# ProDoc__V4_0_2025-09-29.net
KiCad netlist of a schematic drawn in EasyEDA Pro
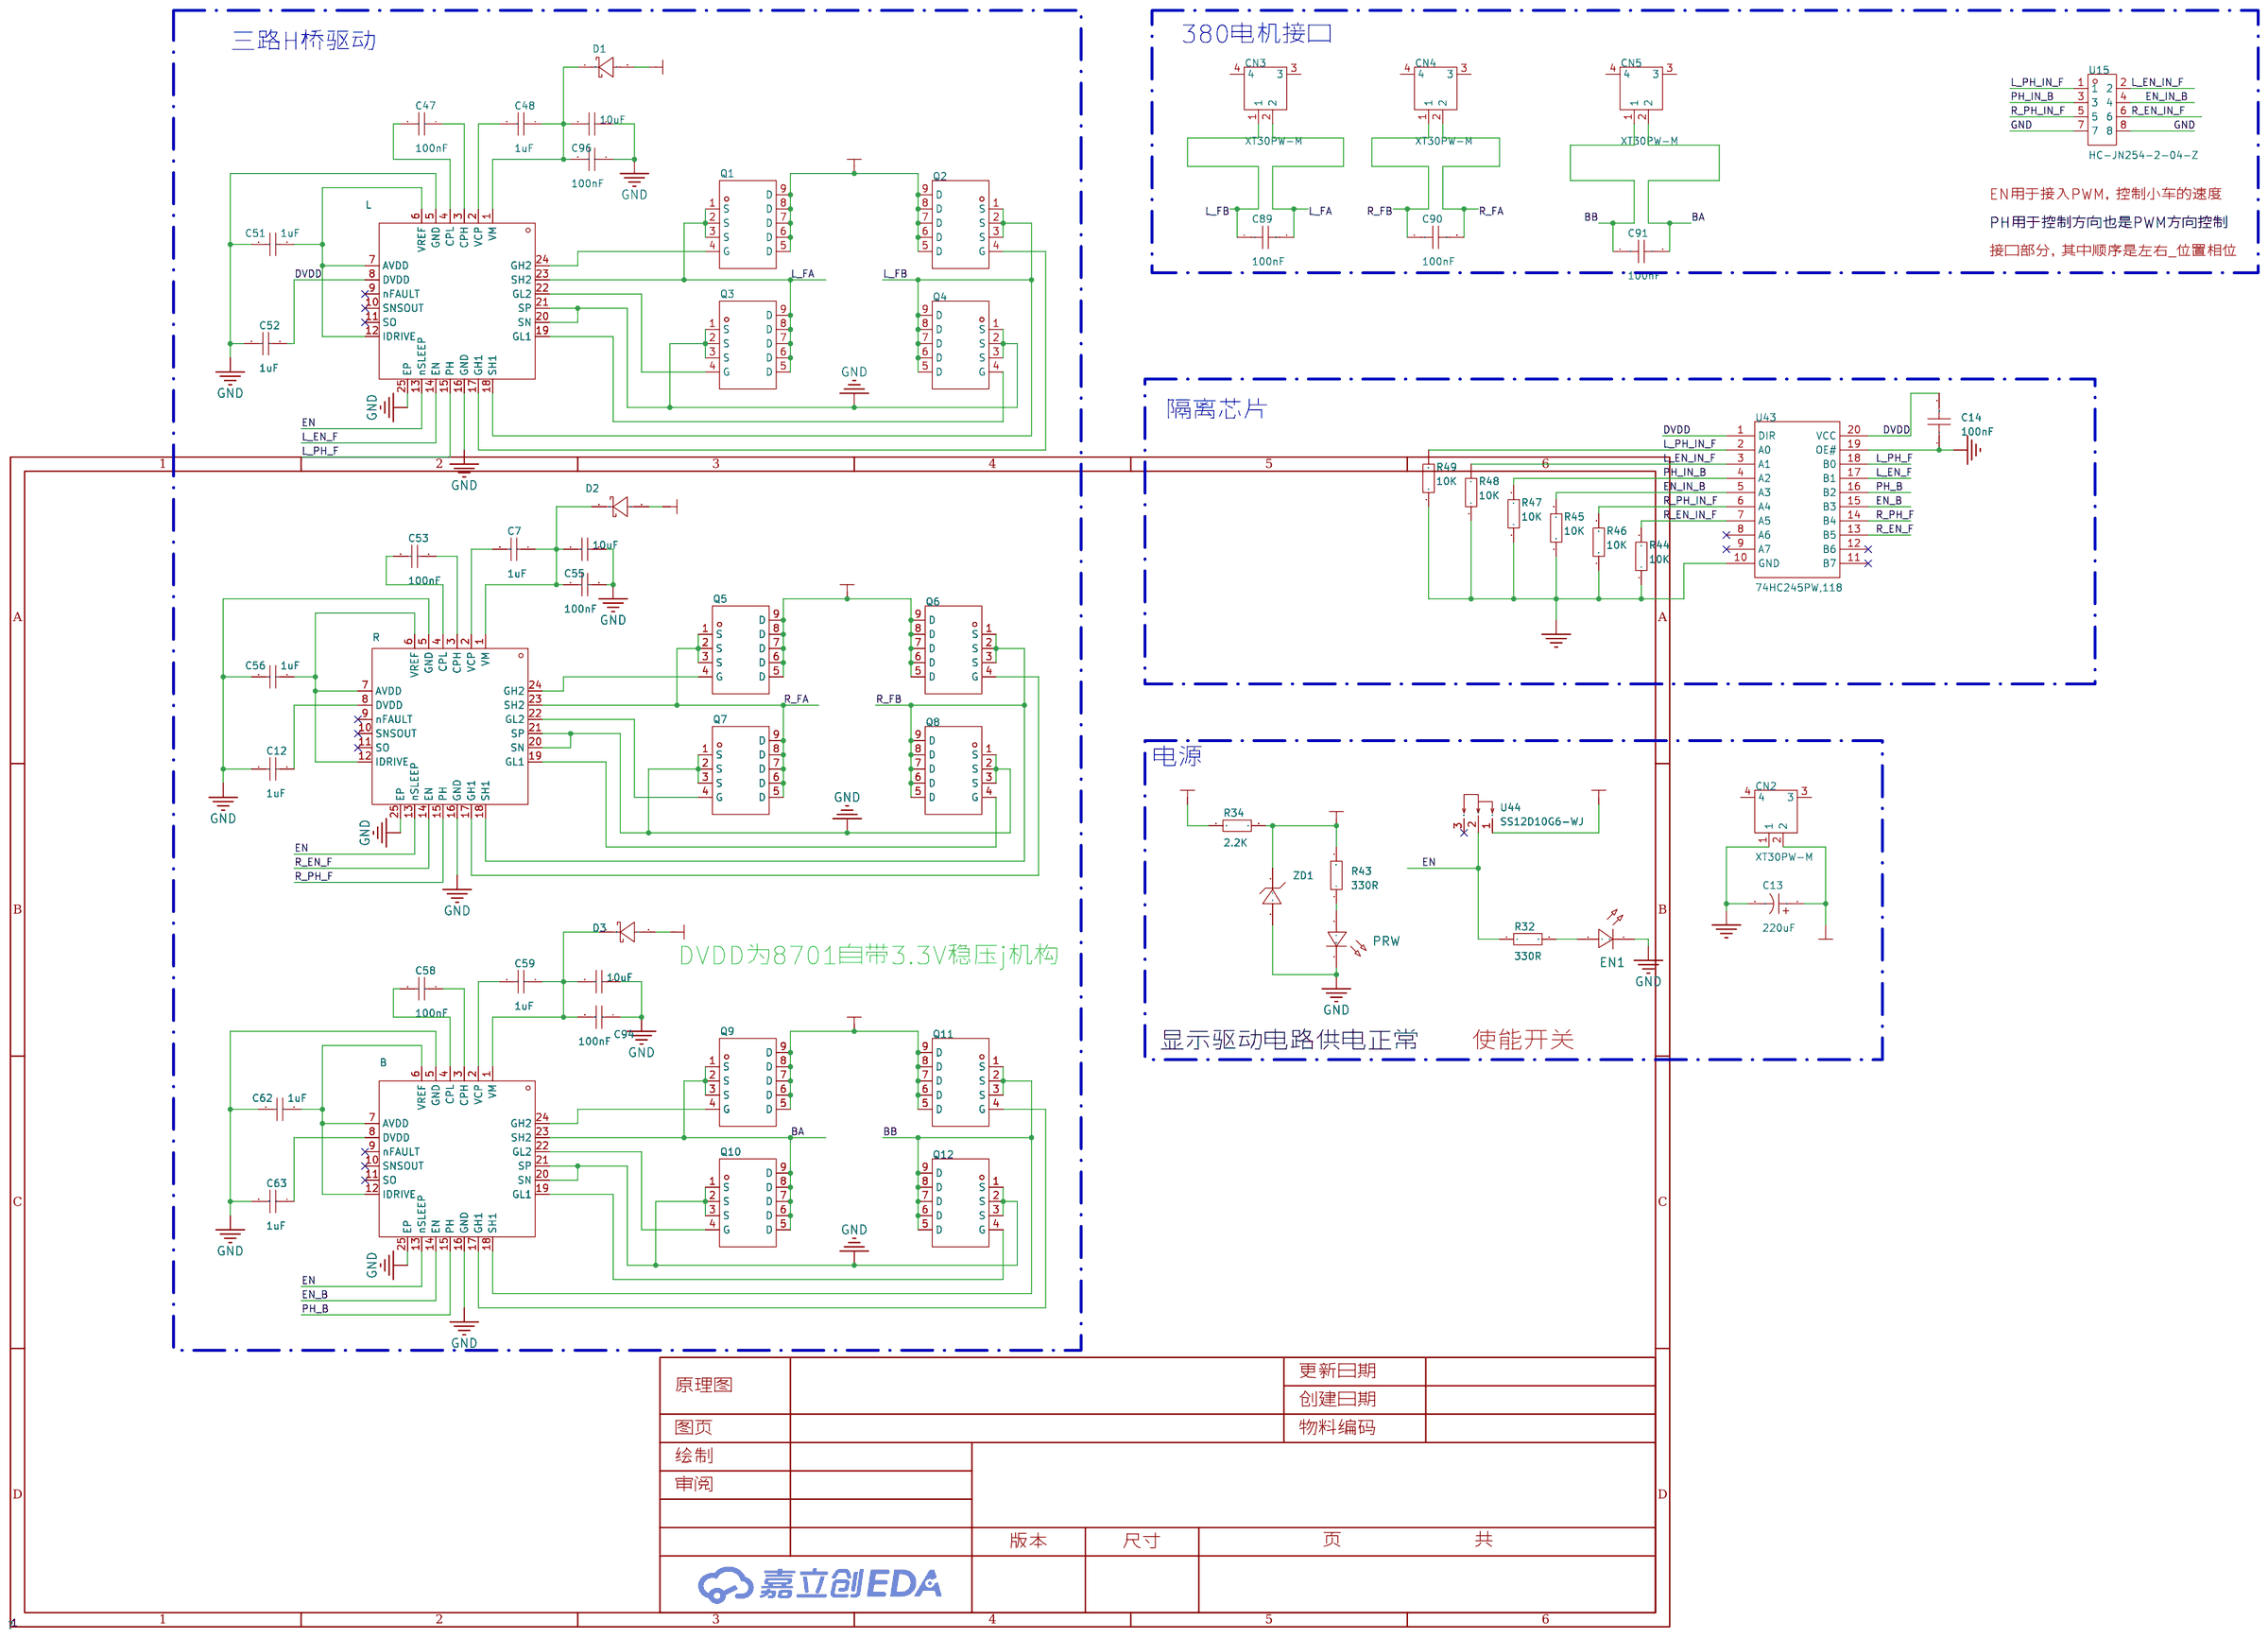
[diagram p0: schematic sheet]

(export (version "E")
  (design (tool "Eeschema 10.0.6"))
  (components
    (comp (ref "B")
      (value "DRV8701ERGET")
      (footprint "easyedapro:VQFN-24_L4.0-W4.0-P0.50-LS4.0-BL-EP")
      (description "DRV8701 DRV8701 H 桥栅极驱动器")
      (fields (field (name "Manufacturer") "TI(德州仪器)"))
      (libsource (lib "easyedapro") (part "DRV8701ERGET"))
    )
    (comp (ref "C7")
      (value "1uF")
      (footprint "easyedapro:C0805")
      (description "容值:100nF;精度:±10%;额定电压:50V;温度系数:X7R;")
      (fields
        (field (name "Manufacturer Part") "CC0805KRX7R9BB104")
        (field (name "Manufacturer") "YAGEO(国巨)")
      )
      (libsource (lib "easyedapro") (part "CC0805KRX7R9BB104"))
    )
    (comp (ref "C12")
      (value "1uF")
      (footprint "easyedapro:C0805")
      (description "容值:100nF;精度:±10%;额定电压:50V;温度系数:X7R;")
      (fields
        (field (name "Manufacturer Part") "CC0805KRX7R9BB104")
        (field (name "Manufacturer") "YAGEO(国巨)")
      )
      (libsource (lib "easyedapro") (part "CC0805KRX7R9BB104"))
    )
    (comp (ref "C13")
      (value "220uF")
      (footprint "easyedapro:CAP-TH_BD8.0-P3.50-D0.5-FD")
      (description "容值:220uF;精度:±20%;额定电压:35V;纹波电流:280mA@120kHz;等效串联电阻:-;")
      (fields (field (name "Manufacturer Part") "01EC1230") (field (name "Manufacturer") "KNSCHA(科尼盛)"))
      (libsource (lib "easyedapro") (part "01EC1230"))
    )
    (comp (ref "C14")
      (value "100nF")
      (footprint "easyedapro:C0805")
      (libsource (lib "easyedapro") (part "CapAcitance"))
    )
    (comp (ref "C47")
      (value "100nF")
      (footprint "easyedapro:C0805")
      (description "容值:100nF;精度:±10%;额定电压:50V;温度系数:X7R;")
      (fields
        (field (name "Manufacturer Part") "CC0805KRX7R9BB104")
        (field (name "Manufacturer") "YAGEO(国巨)")
      )
      (libsource (lib "easyedapro") (part "CC0805KRX7R9BB104"))
    )
    (comp (ref "C48")
      (value "1uF")
      (footprint "easyedapro:C0805")
      (description "容值:100nF;精度:±10%;额定电压:50V;温度系数:X7R;")
      (fields
        (field (name "Manufacturer Part") "CC0805KRX7R9BB104")
        (field (name "Manufacturer") "YAGEO(国巨)")
      )
      (libsource (lib "easyedapro") (part "CC0805KRX7R9BB104"))
    )
    (comp (ref "C51")
      (value "1uF")
      (footprint "easyedapro:C0805")
      (description "容值:100nF;精度:±10%;额定电压:50V;温度系数:X7R;")
      (fields
        (field (name "Manufacturer Part") "CC0805KRX7R9BB104")
        (field (name "Manufacturer") "YAGEO(国巨)")
      )
      (libsource (lib "easyedapro") (part "CC0805KRX7R9BB104"))
    )
    (comp (ref "C52")
      (value "1uF")
      (footprint "easyedapro:C0805")
      (description "容值:100nF;精度:±10%;额定电压:50V;温度系数:X7R;")
      (fields
        (field (name "Manufacturer Part") "CC0805KRX7R9BB104")
        (field (name "Manufacturer") "YAGEO(国巨)")
      )
      (libsource (lib "easyedapro") (part "CC0805KRX7R9BB104"))
    )
    (comp (ref "C53")
      (value "100nF")
      (footprint "easyedapro:C0805")
      (description "容值:100nF;精度:±10%;额定电压:50V;温度系数:X7R;")
      (fields
        (field (name "Manufacturer Part") "CC0805KRX7R9BB104")
        (field (name "Manufacturer") "YAGEO(国巨)")
      )
      (libsource (lib "easyedapro") (part "CC0805KRX7R9BB104"))
    )
    (comp (ref "C54")
      (value "10uF")
      (footprint "easyedapro:C0805")
      (description "容值:100nF;精度:±10%;额定电压:50V;温度系数:X7R;")
      (fields
        (field (name "Manufacturer Part") "CC0805KRX7R9BB104")
        (field (name "Manufacturer") "YAGEO(国巨)")
      )
      (libsource (lib "easyedapro") (part "CC0805KRX7R9BB104"))
    )
    (comp (ref "C55")
      (value "100nF")
      (footprint "easyedapro:C0805")
      (description "容值:100nF;精度:±10%;额定电压:50V;温度系数:X7R;")
      (fields
        (field (name "Manufacturer Part") "CC0805KRX7R9BB104")
        (field (name "Manufacturer") "YAGEO(国巨)")
      )
      (libsource (lib "easyedapro") (part "CC0805KRX7R9BB104"))
    )
    (comp (ref "C56")
      (value "1uF")
      (footprint "easyedapro:C0805")
      (description "容值:100nF;精度:±10%;额定电压:50V;温度系数:X7R;")
      (fields
        (field (name "Manufacturer Part") "CC0805KRX7R9BB104")
        (field (name "Manufacturer") "YAGEO(国巨)")
      )
      (libsource (lib "easyedapro") (part "CC0805KRX7R9BB104"))
    )
    (comp (ref "C58")
      (value "100nF")
      (footprint "easyedapro:C0805")
      (description "容值:100nF;精度:±10%;额定电压:50V;温度系数:X7R;")
      (fields
        (field (name "Manufacturer Part") "CC0805KRX7R9BB104")
        (field (name "Manufacturer") "YAGEO(国巨)")
      )
      (libsource (lib "easyedapro") (part "CC0805KRX7R9BB104"))
    )
    (comp (ref "C59")
      (value "1uF")
      (footprint "easyedapro:C0805")
      (description "容值:100nF;精度:±10%;额定电压:50V;温度系数:X7R;")
      (fields
        (field (name "Manufacturer Part") "CC0805KRX7R9BB104")
        (field (name "Manufacturer") "YAGEO(国巨)")
      )
      (libsource (lib "easyedapro") (part "CC0805KRX7R9BB104"))
    )
    (comp (ref "C62")
      (value "1uF")
      (footprint "easyedapro:C0805")
      (description "容值:100nF;精度:±10%;额定电压:50V;温度系数:X7R;")
      (fields
        (field (name "Manufacturer Part") "CC0805KRX7R9BB104")
        (field (name "Manufacturer") "YAGEO(国巨)")
      )
      (libsource (lib "easyedapro") (part "CC0805KRX7R9BB104"))
    )
    (comp (ref "C63")
      (value "1uF")
      (footprint "easyedapro:C0805")
      (description "容值:100nF;精度:±10%;额定电压:50V;温度系数:X7R;")
      (fields
        (field (name "Manufacturer Part") "CC0805KRX7R9BB104")
        (field (name "Manufacturer") "YAGEO(国巨)")
      )
      (libsource (lib "easyedapro") (part "CC0805KRX7R9BB104"))
    )
    (comp (ref "C89")
      (value "100nF")
      (footprint "easyedapro:C0805")
      (libsource (lib "easyedapro") (part "CapAcitance"))
    )
    (comp (ref "C90")
      (value "100nF")
      (footprint "easyedapro:C0805")
      (libsource (lib "easyedapro") (part "CapAcitance"))
    )
    (comp (ref "C91")
      (value "100nF")
      (footprint "easyedapro:C0805")
      (libsource (lib "easyedapro") (part "CapAcitance"))
    )
    (comp (ref "C93")
      (value "10uF")
      (footprint "easyedapro:C0805")
      (description "容值:100nF;精度:±10%;额定电压:50V;温度系数:X7R;")
      (fields
        (field (name "Manufacturer Part") "CC0805KRX7R9BB104")
        (field (name "Manufacturer") "YAGEO(国巨)")
      )
      (libsource (lib "easyedapro") (part "CC0805KRX7R9BB104"))
    )
    (comp (ref "C94")
      (value "100nF")
      (footprint "easyedapro:C0805")
      (description "容值:100nF;精度:±10%;额定电压:50V;温度系数:X7R;")
      (fields
        (field (name "Manufacturer Part") "CC0805KRX7R9BB104")
        (field (name "Manufacturer") "YAGEO(国巨)")
      )
      (libsource (lib "easyedapro") (part "CC0805KRX7R9BB104"))
    )
    (comp (ref "C95")
      (value "10uF")
      (footprint "easyedapro:C0805")
      (description "容值:100nF;精度:±10%;额定电压:50V;温度系数:X7R;")
      (fields
        (field (name "Manufacturer Part") "CC0805KRX7R9BB104")
        (field (name "Manufacturer") "YAGEO(国巨)")
      )
      (libsource (lib "easyedapro") (part "CC0805KRX7R9BB104"))
    )
    (comp (ref "C96")
      (value "100nF")
      (footprint "easyedapro:C0805")
      (description "容值:100nF;精度:±10%;额定电压:50V;温度系数:X7R;")
      (fields
        (field (name "Manufacturer Part") "CC0805KRX7R9BB104")
        (field (name "Manufacturer") "YAGEO(国巨)")
      )
      (libsource (lib "easyedapro") (part "CC0805KRX7R9BB104"))
    )
    (comp (ref "CN2")
      (value "XT30PW-M")
      (footprint "easyedapro:CONN-TH_XT30PW-M")
      (description "类别:-;类型1:-;")
      (fields (field (name "Manufacturer") "AMASS(艾迈斯)"))
      (libsource (lib "easyedapro") (part "XT30PW-M"))
    )
    (comp (ref "CN3")
      (value "XT30PW-M")
      (footprint "easyedapro:CONN-TH_XT30PW-M")
      (description "类别:-;类型1:-;")
      (fields (field (name "Manufacturer") "AMASS(艾迈斯)"))
      (libsource (lib "easyedapro") (part "XT30PW-M"))
    )
    (comp (ref "CN4")
      (value "XT30PW-M")
      (footprint "easyedapro:CONN-TH_XT30PW-M")
      (description "类别:-;类型1:-;")
      (fields (field (name "Manufacturer") "AMASS(艾迈斯)"))
      (libsource (lib "easyedapro") (part "XT30PW-M"))
    )
    (comp (ref "CN5")
      (value "XT30PW-M")
      (footprint "easyedapro:CONN-TH_XT30PW-M")
      (description "类别:-;类型1:-;")
      (fields (field (name "Manufacturer") "AMASS(艾迈斯)"))
      (libsource (lib "easyedapro") (part "XT30PW-M"))
    )
    (comp (ref "D1")
      (value "1N5819WS")
      (footprint "easyedapro:SOD-323_L1.6-W1.3-LS2.7-RD")
      (description "二极管配置:独立式;直流反向耐压(Vr):40V;平均整流电流(Io):-;正向压降(Vf):600mV@200mA;反向电流(Ir):5A@30V;")
      (fields (field (name "Manufacturer") "YFW佑风微"))
      (libsource (lib "easyedapro") (part "1N5819WS_C1884554"))
    )
    (comp (ref "D2")
      (value "1N5819WS")
      (footprint "easyedapro:SOD-323_L1.6-W1.3-LS2.7-RD")
      (description "二极管配置:独立式;直流反向耐压(Vr):40V;平均整流电流(Io):-;正向压降(Vf):600mV@200mA;反向电流(Ir):5A@30V;")
      (fields (field (name "Manufacturer") "YFW佑风微"))
      (libsource (lib "easyedapro") (part "1N5819WS_C1884554"))
    )
    (comp (ref "D3")
      (value "1N5819WS")
      (footprint "easyedapro:SOD-323_L1.6-W1.3-LS2.7-RD")
      (description "二极管配置:独立式;直流反向耐压(Vr):40V;平均整流电流(Io):-;正向压降(Vf):600mV@200mA;反向电流(Ir):5A@30V;")
      (fields (field (name "Manufacturer") "YFW佑风微"))
      (libsource (lib "easyedapro") (part "1N5819WS_C1884554"))
    )
    (comp (ref "EN1")
      (value "~")
      (footprint "easyedapro:LED0603-RD_BLUE")
      (libsource (lib "easyedapro") (part "LED_R"))
    )
    (comp (ref "L")
      (value "DRV8701ERGET")
      (footprint "easyedapro:VQFN-24_L4.0-W4.0-P0.50-LS4.0-BL-EP")
      (description "DRV8701 DRV8701 H 桥栅极驱动器")
      (fields (field (name "Manufacturer") "TI(德州仪器)"))
      (libsource (lib "easyedapro") (part "DRV8701ERGET"))
    )
    (comp (ref "PRW")
      (value "~")
      (footprint "easyedapro:LED0603-RD_BLUE")
      (libsource (lib "easyedapro") (part "LED_R"))
    )
    (comp (ref "Q1")
      (value "TPH1R403NL")
      (footprint "easyedapro:DSOP-8_L5.0-W5.0-P1.27-LS6.0-BL-EP")
      (fields (field (name "Manufacturer") "TOSHIBA(东芝)"))
      (libsource (lib "easyedapro") (part "TPH1R403NL"))
    )
    (comp (ref "Q2")
      (value "TPH1R403NL")
      (footprint "easyedapro:DSOP-8_L5.0-W5.0-P1.27-LS6.0-BL-EP")
      (fields (field (name "Manufacturer") "TOSHIBA(东芝)"))
      (libsource (lib "easyedapro") (part "TPH1R403NL"))
    )
    (comp (ref "Q3")
      (value "TPH1R403NL")
      (footprint "easyedapro:DSOP-8_L5.0-W5.0-P1.27-LS6.0-BL-EP")
      (fields (field (name "Manufacturer") "TOSHIBA(东芝)"))
      (libsource (lib "easyedapro") (part "TPH1R403NL"))
    )
    (comp (ref "Q4")
      (value "TPH1R403NL")
      (footprint "easyedapro:DSOP-8_L5.0-W5.0-P1.27-LS6.0-BL-EP")
      (fields (field (name "Manufacturer") "TOSHIBA(东芝)"))
      (libsource (lib "easyedapro") (part "TPH1R403NL"))
    )
    (comp (ref "Q5")
      (value "TPH1R403NL")
      (footprint "easyedapro:DSOP-8_L5.0-W5.0-P1.27-LS6.0-BL-EP")
      (fields (field (name "Manufacturer") "TOSHIBA(东芝)"))
      (libsource (lib "easyedapro") (part "TPH1R403NL"))
    )
    (comp (ref "Q6")
      (value "TPH1R403NL")
      (footprint "easyedapro:DSOP-8_L5.0-W5.0-P1.27-LS6.0-BL-EP")
      (fields (field (name "Manufacturer") "TOSHIBA(东芝)"))
      (libsource (lib "easyedapro") (part "TPH1R403NL"))
    )
    (comp (ref "Q7")
      (value "TPH1R403NL")
      (footprint "easyedapro:DSOP-8_L5.0-W5.0-P1.27-LS6.0-BL-EP")
      (fields (field (name "Manufacturer") "TOSHIBA(东芝)"))
      (libsource (lib "easyedapro") (part "TPH1R403NL"))
    )
    (comp (ref "Q8")
      (value "TPH1R403NL")
      (footprint "easyedapro:DSOP-8_L5.0-W5.0-P1.27-LS6.0-BL-EP")
      (fields (field (name "Manufacturer") "TOSHIBA(东芝)"))
      (libsource (lib "easyedapro") (part "TPH1R403NL"))
    )
    (comp (ref "Q9")
      (value "TPH1R403NL")
      (footprint "easyedapro:DSOP-8_L5.0-W5.0-P1.27-LS6.0-BL-EP")
      (fields (field (name "Manufacturer") "TOSHIBA(东芝)"))
      (libsource (lib "easyedapro") (part "TPH1R403NL"))
    )
    (comp (ref "Q10")
      (value "TPH1R403NL")
      (footprint "easyedapro:DSOP-8_L5.0-W5.0-P1.27-LS6.0-BL-EP")
      (fields (field (name "Manufacturer") "TOSHIBA(东芝)"))
      (libsource (lib "easyedapro") (part "TPH1R403NL"))
    )
    (comp (ref "Q11")
      (value "TPH1R403NL")
      (footprint "easyedapro:DSOP-8_L5.0-W5.0-P1.27-LS6.0-BL-EP")
      (fields (field (name "Manufacturer") "TOSHIBA(东芝)"))
      (libsource (lib "easyedapro") (part "TPH1R403NL"))
    )
    (comp (ref "Q12")
      (value "TPH1R403NL")
      (footprint "easyedapro:DSOP-8_L5.0-W5.0-P1.27-LS6.0-BL-EP")
      (fields (field (name "Manufacturer") "TOSHIBA(东芝)"))
      (libsource (lib "easyedapro") (part "TPH1R403NL"))
    )
    (comp (ref "R")
      (value "DRV8701ERGET")
      (footprint "easyedapro:VQFN-24_L4.0-W4.0-P0.50-LS4.0-BL-EP")
      (description "DRV8701 DRV8701 H 桥栅极驱动器")
      (fields (field (name "Manufacturer") "TI(德州仪器)"))
      (libsource (lib "easyedapro") (part "DRV8701ERGET"))
    )
    (comp (ref "R32")
      (value "330R")
      (footprint "easyedapro:R0603")
      (libsource (lib "easyedapro") (part "电阻"))
    )
    (comp (ref "R34")
      (value "2.2K")
      (footprint "easyedapro:R0603")
      (libsource (lib "easyedapro") (part "电阻"))
    )
    (comp (ref "R43")
      (value "330R")
      (footprint "easyedapro:R0603")
      (libsource (lib "easyedapro") (part "电阻"))
    )
    (comp (ref "R44") (value "10K") (footprint "easyedapro:R0603") (libsource (lib "easyedapro") (part "电阻")))
    (comp (ref "R45") (value "10K") (footprint "easyedapro:R0603") (libsource (lib "easyedapro") (part "电阻")))
    (comp (ref "R46") (value "10K") (footprint "easyedapro:R0603") (libsource (lib "easyedapro") (part "电阻")))
    (comp (ref "R47") (value "10K") (footprint "easyedapro:R0603") (libsource (lib "easyedapro") (part "电阻")))
    (comp (ref "R48") (value "10K") (footprint "easyedapro:R0603") (libsource (lib "easyedapro") (part "电阻")))
    (comp (ref "R49") (value "10K") (footprint "easyedapro:R0603") (libsource (lib "easyedapro") (part "电阻")))
    (comp (ref "U15")
      (value "HC-JN254-2-04-Z")
      (footprint "easyedapro:IDC-TH_8P-P2.54-V-R2-C4-S2.54")
      (fields (field (name "Manufacturer") "HCTL(华灿天禄)"))
      (libsource (lib "easyedapro") (part "HC-JN254-2-04-Z"))
    )
    (comp (ref "U43")
      (value "74HC245PW,118")
      (footprint "easyedapro:TSSOP-20_L6.5-W4.4-P0.65-LS6.4-BL")
      (description "输入类型:-;电源电压:2V~6V;元件数:1;每个元件位数:8;灌电流(IOL):7.8mA;拉电流(IOH):7.8mA;")
      (fields (field (name "Manufacturer") "Nexperia(安世)"))
      (libsource (lib "easyedapro") (part "74HC245PW,118"))
    )
    (comp (ref "U44")
      (value "SS12D10G6-WJ")
      (footprint "easyedapro:SW-TH_3P-P4.80_HX-SS12D10G6-WJ")
      (description "电路结构:单刀双掷;安装方式:弯插;开关颜色:黑色;额定电流:2A;额定电压:125V;工作寿命:3千次;")
      (fields (field (name "Manufacturer") "SHOU HAN(首韩)"))
      (libsource (lib "easyedapro") (part "SS12D10G6-WJ"))
    )
    (comp (ref "ZD1")
      (value "BZT52C3V3")
      (footprint "easyedapro:SOD-123_L2.8-W1.8-LS3.7-RD")
      (description "二极管配置:独立式;稳压值(标称值):3.3V;稳压值(范围):3.1V~3.5V;精度:-;功率:350mW;反向电流(Ir):5A@1V;阻抗(Zzt):95Ω;")
      (fields (field (name "Manufacturer") "CJ（江苏长电/长晶）"))
      (libsource (lib "easyedapro") (part "BZT52C3V3_C2112"))
    )
  )
  (nets
    (net (code "1") (name "/BA") (class "Default")
      (node (ref "B") (pin "23") (pinfunction "SH2_23") (pintype "input"))
      (node (ref "C91") (pin "2") (pinfunction "2_2") (pintype "input"))
      (node (ref "CN5") (pin "2") (pinfunction "2_2") (pintype "unspecified"))
      (node (ref "Q10") (pin "5") (pinfunction "D_5") (pintype "input"))
      (node (ref "Q10") (pin "6") (pinfunction "D_6") (pintype "input"))
      (node (ref "Q10") (pin "7") (pinfunction "D_7") (pintype "input"))
      (node (ref "Q10") (pin "8") (pinfunction "D_8") (pintype "input"))
      (node (ref "Q10") (pin "9") (pinfunction "D_9") (pintype "input"))
      (node (ref "Q9") (pin "1") (pinfunction "S_1") (pintype "input"))
      (node (ref "Q9") (pin "2") (pinfunction "S_2") (pintype "input"))
      (node (ref "Q9") (pin "3") (pinfunction "S_3") (pintype "input"))
    )
    (net (code "2") (name "/BB") (class "Default")
      (node (ref "B") (pin "18") (pinfunction "SH1_18") (pintype "input"))
      (node (ref "C91") (pin "1") (pinfunction "1_1") (pintype "input"))
      (node (ref "CN5") (pin "1") (pinfunction "1_1") (pintype "unspecified"))
      (node (ref "Q11") (pin "1") (pinfunction "S_1") (pintype "input"))
      (node (ref "Q11") (pin "2") (pinfunction "S_2") (pintype "input"))
      (node (ref "Q11") (pin "3") (pinfunction "S_3") (pintype "input"))
      (node (ref "Q12") (pin "5") (pinfunction "D_5") (pintype "input"))
      (node (ref "Q12") (pin "6") (pinfunction "D_6") (pintype "input"))
      (node (ref "Q12") (pin "7") (pinfunction "D_7") (pintype "input"))
      (node (ref "Q12") (pin "8") (pinfunction "D_8") (pintype "input"))
      (node (ref "Q12") (pin "9") (pinfunction "D_9") (pintype "input"))
    )
    (net (code "3") (name "/DVDD") (class "Default")
      (node (ref "C14") (pin "2") (pinfunction "2_2") (pintype "input"))
      (node (ref "C52") (pin "1") (pinfunction "1_1") (pintype "input"))
      (node (ref "L") (pin "8") (pinfunction "DVDD_8") (pintype "input"))
      (node (ref "U43") (pin "1") (pinfunction "DIR_1") (pintype "unspecified"))
      (node (ref "U43") (pin "20") (pinfunction "VCC_20") (pintype "unspecified"))
    )
    (net (code "4") (name "/EN") (class "Default")
      (node (ref "B") (pin "13") (pinfunction "nSLEEP_13") (pintype "input"))
      (node (ref "L") (pin "13") (pinfunction "nSLEEP_13") (pintype "input"))
      (node (ref "R") (pin "13") (pinfunction "nSLEEP_13") (pintype "input"))
      (node (ref "R32") (pin "1") (pinfunction "1_1") (pintype "input"))
      (node (ref "U44") (pin "2") (pinfunction "2_2") (pintype "unspecified"))
    )
    (net (code "5") (name "/EN_B") (class "Default")
      (node (ref "B") (pin "14") (pinfunction "EN_14") (pintype "input"))
      (node (ref "U43") (pin "15") (pinfunction "B3_15") (pintype "unspecified"))
    )
    (net (code "6") (name "/EN_IN_B") (class "Default")
      (node (ref "R45") (pin "2") (pinfunction "2_2") (pintype "input"))
      (node (ref "U15") (pin "4") (pinfunction "4_4") (pintype "unspecified"))
      (node (ref "U43") (pin "5") (pinfunction "A3_5") (pintype "unspecified"))
    )
    (net (code "7") (name "/L_EN_F") (class "Default")
      (node (ref "L") (pin "14") (pinfunction "EN_14") (pintype "input"))
      (node (ref "U43") (pin "17") (pinfunction "B1_17") (pintype "unspecified"))
    )
    (net (code "8") (name "/L_EN_IN_F") (class "Default")
      (node (ref "R48") (pin "2") (pinfunction "2_2") (pintype "input"))
      (node (ref "U15") (pin "2") (pinfunction "2_2") (pintype "unspecified"))
      (node (ref "U43") (pin "3") (pinfunction "A1_3") (pintype "unspecified"))
    )
    (net (code "9") (name "/L_FA") (class "Default")
      (node (ref "C89") (pin "2") (pinfunction "2_2") (pintype "input"))
      (node (ref "CN3") (pin "2") (pinfunction "2_2") (pintype "unspecified"))
      (node (ref "L") (pin "23") (pinfunction "SH2_23") (pintype "input"))
      (node (ref "Q1") (pin "1") (pinfunction "S_1") (pintype "input"))
      (node (ref "Q1") (pin "2") (pinfunction "S_2") (pintype "input"))
      (node (ref "Q1") (pin "3") (pinfunction "S_3") (pintype "input"))
      (node (ref "Q3") (pin "5") (pinfunction "D_5") (pintype "input"))
      (node (ref "Q3") (pin "6") (pinfunction "D_6") (pintype "input"))
      (node (ref "Q3") (pin "7") (pinfunction "D_7") (pintype "input"))
      (node (ref "Q3") (pin "8") (pinfunction "D_8") (pintype "input"))
      (node (ref "Q3") (pin "9") (pinfunction "D_9") (pintype "input"))
    )
    (net (code "10") (name "/L_FB") (class "Default")
      (node (ref "C89") (pin "1") (pinfunction "1_1") (pintype "input"))
      (node (ref "CN3") (pin "1") (pinfunction "1_1") (pintype "unspecified"))
      (node (ref "L") (pin "18") (pinfunction "SH1_18") (pintype "input"))
      (node (ref "Q2") (pin "1") (pinfunction "S_1") (pintype "input"))
      (node (ref "Q2") (pin "2") (pinfunction "S_2") (pintype "input"))
      (node (ref "Q2") (pin "3") (pinfunction "S_3") (pintype "input"))
      (node (ref "Q4") (pin "5") (pinfunction "D_5") (pintype "input"))
      (node (ref "Q4") (pin "6") (pinfunction "D_6") (pintype "input"))
      (node (ref "Q4") (pin "7") (pinfunction "D_7") (pintype "input"))
      (node (ref "Q4") (pin "8") (pinfunction "D_8") (pintype "input"))
      (node (ref "Q4") (pin "9") (pinfunction "D_9") (pintype "input"))
    )
    (net (code "11") (name "/L_PH_F") (class "Default")
      (node (ref "L") (pin "15") (pinfunction "PH_15") (pintype "input"))
      (node (ref "U43") (pin "18") (pinfunction "B0_18") (pintype "unspecified"))
    )
    (net (code "12") (name "/L_PH_IN_F") (class "Default")
      (node (ref "R49") (pin "2") (pinfunction "2_2") (pintype "input"))
      (node (ref "U15") (pin "1") (pinfunction "1_1") (pintype "unspecified"))
      (node (ref "U43") (pin "2") (pinfunction "A0_2") (pintype "unspecified"))
    )
    (net (code "13") (name "/PH_B") (class "Default")
      (node (ref "B") (pin "15") (pinfunction "PH_15") (pintype "input"))
      (node (ref "U43") (pin "16") (pinfunction "B2_16") (pintype "unspecified"))
    )
    (net (code "14") (name "/PH_IN_B") (class "Default")
      (node (ref "R47") (pin "2") (pinfunction "2_2") (pintype "input"))
      (node (ref "U15") (pin "3") (pinfunction "3_3") (pintype "unspecified"))
      (node (ref "U43") (pin "4") (pinfunction "A2_4") (pintype "unspecified"))
    )
    (net (code "15") (name "/R_EN_F") (class "Default")
      (node (ref "R") (pin "14") (pinfunction "EN_14") (pintype "input"))
      (node (ref "U43") (pin "13") (pinfunction "B5_13") (pintype "unspecified"))
    )
    (net (code "16") (name "/R_EN_IN_F") (class "Default")
      (node (ref "R44") (pin "2") (pinfunction "2_2") (pintype "input"))
      (node (ref "U15") (pin "6") (pinfunction "6_6") (pintype "unspecified"))
      (node (ref "U43") (pin "7") (pinfunction "A5_7") (pintype "unspecified"))
    )
    (net (code "17") (name "/R_FA") (class "Default")
      (node (ref "C90") (pin "2") (pinfunction "2_2") (pintype "input"))
      (node (ref "CN4") (pin "2") (pinfunction "2_2") (pintype "unspecified"))
      (node (ref "Q5") (pin "1") (pinfunction "S_1") (pintype "input"))
      (node (ref "Q5") (pin "2") (pinfunction "S_2") (pintype "input"))
      (node (ref "Q5") (pin "3") (pinfunction "S_3") (pintype "input"))
      (node (ref "Q7") (pin "5") (pinfunction "D_5") (pintype "input"))
      (node (ref "Q7") (pin "6") (pinfunction "D_6") (pintype "input"))
      (node (ref "Q7") (pin "7") (pinfunction "D_7") (pintype "input"))
      (node (ref "Q7") (pin "8") (pinfunction "D_8") (pintype "input"))
      (node (ref "Q7") (pin "9") (pinfunction "D_9") (pintype "input"))
      (node (ref "R") (pin "23") (pinfunction "SH2_23") (pintype "input"))
    )
    (net (code "18") (name "/R_FB") (class "Default")
      (node (ref "C90") (pin "1") (pinfunction "1_1") (pintype "input"))
      (node (ref "CN4") (pin "1") (pinfunction "1_1") (pintype "unspecified"))
      (node (ref "Q6") (pin "1") (pinfunction "S_1") (pintype "input"))
      (node (ref "Q6") (pin "2") (pinfunction "S_2") (pintype "input"))
      (node (ref "Q6") (pin "3") (pinfunction "S_3") (pintype "input"))
      (node (ref "Q8") (pin "5") (pinfunction "D_5") (pintype "input"))
      (node (ref "Q8") (pin "6") (pinfunction "D_6") (pintype "input"))
      (node (ref "Q8") (pin "7") (pinfunction "D_7") (pintype "input"))
      (node (ref "Q8") (pin "8") (pinfunction "D_8") (pintype "input"))
      (node (ref "Q8") (pin "9") (pinfunction "D_9") (pintype "input"))
      (node (ref "R") (pin "18") (pinfunction "SH1_18") (pintype "input"))
    )
    (net (code "19") (name "/R_PH_F") (class "Default")
      (node (ref "R") (pin "15") (pinfunction "PH_15") (pintype "input"))
      (node (ref "U43") (pin "14") (pinfunction "B4_14") (pintype "unspecified"))
    )
    (net (code "20") (name "/R_PH_IN_F") (class "Default")
      (node (ref "R46") (pin "2") (pinfunction "2_2") (pintype "input"))
      (node (ref "U15") (pin "5") (pinfunction "5_5") (pintype "unspecified"))
      (node (ref "U43") (pin "6") (pinfunction "A4_6") (pintype "unspecified"))
    )
    (net (code "21") (name "3.3V") (class "Default")
      (node (ref "R34") (pin "2") (pinfunction "2_2") (pintype "input"))
      (node (ref "R43") (pin "2") (pinfunction "2_2") (pintype "input"))
      (node (ref "U44") (pin "1") (pinfunction "1_1") (pintype "unspecified"))
      (node (ref "ZD1") (pin "1") (pinfunction "K_1") (pintype "input"))
    )
    (net (code "22") (name "GND") (class "Default")
      (node (ref "B") (pin "16") (pinfunction "GND_16") (pintype "input"))
      (node (ref "B") (pin "20") (pinfunction "SN_20") (pintype "input"))
      (node (ref "B") (pin "21") (pinfunction "SP_21") (pintype "input"))
      (node (ref "B") (pin "25") (pinfunction "EP_25") (pintype "input"))
      (node (ref "B") (pin "5") (pinfunction "GND_5") (pintype "input"))
      (node (ref "C12") (pin "2") (pinfunction "2_2") (pintype "input"))
      (node (ref "C13") (pin "2") (pinfunction "2_2") (pintype "input"))
      (node (ref "C14") (pin "1") (pinfunction "1_1") (pintype "input"))
      (node (ref "C51") (pin "2") (pinfunction "2_2") (pintype "input"))
      (node (ref "C52") (pin "2") (pinfunction "2_2") (pintype "input"))
      (node (ref "C54") (pin "1") (pinfunction "1_1") (pintype "input"))
      (node (ref "C55") (pin "1") (pinfunction "1_1") (pintype "input"))
      (node (ref "C56") (pin "2") (pinfunction "2_2") (pintype "input"))
      (node (ref "C62") (pin "2") (pinfunction "2_2") (pintype "input"))
      (node (ref "C63") (pin "2") (pinfunction "2_2") (pintype "input"))
      (node (ref "C93") (pin "1") (pinfunction "1_1") (pintype "input"))
      (node (ref "C94") (pin "1") (pinfunction "1_1") (pintype "input"))
      (node (ref "C95") (pin "1") (pinfunction "1_1") (pintype "input"))
      (node (ref "C96") (pin "1") (pinfunction "1_1") (pintype "input"))
      (node (ref "CN2") (pin "1") (pinfunction "1_1") (pintype "unspecified"))
      (node (ref "EN1") (pin "1") (pinfunction "C_1") (pintype "input"))
      (node (ref "L") (pin "16") (pinfunction "GND_16") (pintype "input"))
      (node (ref "L") (pin "20") (pinfunction "SN_20") (pintype "input"))
      (node (ref "L") (pin "21") (pinfunction "SP_21") (pintype "input"))
      (node (ref "L") (pin "25") (pinfunction "EP_25") (pintype "input"))
      (node (ref "L") (pin "5") (pinfunction "GND_5") (pintype "input"))
      (node (ref "PRW") (pin "1") (pinfunction "C_1") (pintype "input"))
      (node (ref "Q10") (pin "1") (pinfunction "S_1") (pintype "input"))
      (node (ref "Q10") (pin "2") (pinfunction "S_2") (pintype "input"))
      (node (ref "Q10") (pin "3") (pinfunction "S_3") (pintype "input"))
      (node (ref "Q12") (pin "1") (pinfunction "S_1") (pintype "input"))
      (node (ref "Q12") (pin "2") (pinfunction "S_2") (pintype "input"))
      (node (ref "Q12") (pin "3") (pinfunction "S_3") (pintype "input"))
      (node (ref "Q3") (pin "1") (pinfunction "S_1") (pintype "input"))
      (node (ref "Q3") (pin "2") (pinfunction "S_2") (pintype "input"))
      (node (ref "Q3") (pin "3") (pinfunction "S_3") (pintype "input"))
      (node (ref "Q4") (pin "1") (pinfunction "S_1") (pintype "input"))
      (node (ref "Q4") (pin "2") (pinfunction "S_2") (pintype "input"))
      (node (ref "Q4") (pin "3") (pinfunction "S_3") (pintype "input"))
      (node (ref "Q7") (pin "1") (pinfunction "S_1") (pintype "input"))
      (node (ref "Q7") (pin "2") (pinfunction "S_2") (pintype "input"))
      (node (ref "Q7") (pin "3") (pinfunction "S_3") (pintype "input"))
      (node (ref "Q8") (pin "1") (pinfunction "S_1") (pintype "input"))
      (node (ref "Q8") (pin "2") (pinfunction "S_2") (pintype "input"))
      (node (ref "Q8") (pin "3") (pinfunction "S_3") (pintype "input"))
      (node (ref "R") (pin "16") (pinfunction "GND_16") (pintype "input"))
      (node (ref "R") (pin "20") (pinfunction "SN_20") (pintype "input"))
      (node (ref "R") (pin "21") (pinfunction "SP_21") (pintype "input"))
      (node (ref "R") (pin "25") (pinfunction "EP_25") (pintype "input"))
      (node (ref "R") (pin "5") (pinfunction "GND_5") (pintype "input"))
      (node (ref "R44") (pin "1") (pinfunction "1_1") (pintype "input"))
      (node (ref "R45") (pin "1") (pinfunction "1_1") (pintype "input"))
      (node (ref "R46") (pin "1") (pinfunction "1_1") (pintype "input"))
      (node (ref "R47") (pin "1") (pinfunction "1_1") (pintype "input"))
      (node (ref "R48") (pin "1") (pinfunction "1_1") (pintype "input"))
      (node (ref "R49") (pin "1") (pinfunction "1_1") (pintype "input"))
      (node (ref "U15") (pin "7") (pinfunction "7_7") (pintype "unspecified"))
      (node (ref "U15") (pin "8") (pinfunction "8_8") (pintype "unspecified"))
      (node (ref "U43") (pin "10") (pinfunction "GND_10") (pintype "unspecified"))
      (node (ref "U43") (pin "19") (pinfunction "OE#_19") (pintype "unspecified"))
      (node (ref "ZD1") (pin "2") (pinfunction "A_2") (pintype "input"))
    )
    (net (code "23") (name "Net-(B-AVDD)") (class "Default")
      (node (ref "B") (pin "12") (pinfunction "IDRIVE_12") (pintype "input"))
      (node (ref "B") (pin "6") (pinfunction "VREF_6") (pintype "input"))
      (node (ref "B") (pin "7") (pinfunction "AVDD_7") (pintype "input"))
      (node (ref "C62") (pin "1") (pinfunction "1_1") (pintype "input"))
    )
    (net (code "24") (name "Net-(B-CPH)") (class "Default")
      (node (ref "B") (pin "3") (pinfunction "CPH_3") (pintype "input"))
      (node (ref "C58") (pin "1") (pinfunction "1_1") (pintype "input"))
    )
    (net (code "25") (name "Net-(B-CPL)") (class "Default")
      (node (ref "B") (pin "4") (pinfunction "CPL_4") (pintype "input"))
      (node (ref "C58") (pin "2") (pinfunction "2_2") (pintype "input"))
    )
    (net (code "26") (name "Net-(B-DVDD)") (class "Default")
      (node (ref "B") (pin "8") (pinfunction "DVDD_8") (pintype "input"))
      (node (ref "C63") (pin "1") (pinfunction "1_1") (pintype "input"))
    )
    (net (code "27") (name "Net-(B-GH1)") (class "Default")
      (node (ref "B") (pin "17") (pinfunction "GH1_17") (pintype "input"))
      (node (ref "Q11") (pin "4") (pinfunction "G_4") (pintype "input"))
    )
    (net (code "28") (name "Net-(B-GH2)") (class "Default")
      (node (ref "B") (pin "24") (pinfunction "GH2_24") (pintype "input"))
      (node (ref "Q9") (pin "4") (pinfunction "G_4") (pintype "input"))
    )
    (net (code "29") (name "Net-(B-GL1)") (class "Default")
      (node (ref "B") (pin "19") (pinfunction "GL1_19") (pintype "input"))
      (node (ref "Q12") (pin "4") (pinfunction "G_4") (pintype "input"))
    )
    (net (code "30") (name "Net-(B-GL2)") (class "Default")
      (node (ref "B") (pin "22") (pinfunction "GL2_22") (pintype "input"))
      (node (ref "Q10") (pin "4") (pinfunction "G_4") (pintype "input"))
    )
    (net (code "31") (name "Net-(B-VCP)") (class "Default")
      (node (ref "B") (pin "2") (pinfunction "VCP_2") (pintype "input"))
      (node (ref "C59") (pin "2") (pinfunction "2_2") (pintype "input"))
    )
    (net (code "32") (name "Net-(B-VM)") (class "Default")
      (node (ref "B") (pin "1") (pinfunction "VM_1") (pintype "input"))
      (node (ref "C59") (pin "1") (pinfunction "1_1") (pintype "input"))
      (node (ref "C93") (pin "2") (pinfunction "2_2") (pintype "input"))
      (node (ref "C94") (pin "2") (pinfunction "2_2") (pintype "input"))
      (node (ref "D3") (pin "1") (pinfunction "C_1") (pintype "input"))
    )
    (net (code "33") (name "Net-(D1-C)") (class "Default")
      (node (ref "C48") (pin "1") (pinfunction "1_1") (pintype "input"))
      (node (ref "C95") (pin "2") (pinfunction "2_2") (pintype "input"))
      (node (ref "C96") (pin "2") (pinfunction "2_2") (pintype "input"))
      (node (ref "D1") (pin "1") (pinfunction "C_1") (pintype "input"))
      (node (ref "L") (pin "1") (pinfunction "VM_1") (pintype "input"))
    )
    (net (code "34") (name "Net-(D2-C)") (class "Default")
      (node (ref "C54") (pin "2") (pinfunction "2_2") (pintype "input"))
      (node (ref "C55") (pin "2") (pinfunction "2_2") (pintype "input"))
      (node (ref "C7") (pin "1") (pinfunction "1_1") (pintype "input"))
      (node (ref "D2") (pin "1") (pinfunction "C_1") (pintype "input"))
      (node (ref "R") (pin "1") (pinfunction "VM_1") (pintype "input"))
    )
    (net (code "35") (name "Net-(EN1-A)") (class "Default")
      (node (ref "EN1") (pin "2") (pinfunction "A_2") (pintype "input"))
      (node (ref "R32") (pin "2") (pinfunction "2_2") (pintype "input"))
    )
    (net (code "36") (name "Net-(L-AVDD)") (class "Default")
      (node (ref "C51") (pin "1") (pinfunction "1_1") (pintype "input"))
      (node (ref "L") (pin "12") (pinfunction "IDRIVE_12") (pintype "input"))
      (node (ref "L") (pin "6") (pinfunction "VREF_6") (pintype "input"))
      (node (ref "L") (pin "7") (pinfunction "AVDD_7") (pintype "input"))
    )
    (net (code "37") (name "Net-(L-CPH)") (class "Default")
      (node (ref "C47") (pin "1") (pinfunction "1_1") (pintype "input"))
      (node (ref "L") (pin "3") (pinfunction "CPH_3") (pintype "input"))
    )
    (net (code "38") (name "Net-(L-CPL)") (class "Default")
      (node (ref "C47") (pin "2") (pinfunction "2_2") (pintype "input"))
      (node (ref "L") (pin "4") (pinfunction "CPL_4") (pintype "input"))
    )
    (net (code "39") (name "Net-(L-GH1)") (class "Default")
      (node (ref "L") (pin "17") (pinfunction "GH1_17") (pintype "input"))
      (node (ref "Q2") (pin "4") (pinfunction "G_4") (pintype "input"))
    )
    (net (code "40") (name "Net-(L-GH2)") (class "Default")
      (node (ref "L") (pin "24") (pinfunction "GH2_24") (pintype "input"))
      (node (ref "Q1") (pin "4") (pinfunction "G_4") (pintype "input"))
    )
    (net (code "41") (name "Net-(L-GL1)") (class "Default")
      (node (ref "L") (pin "19") (pinfunction "GL1_19") (pintype "input"))
      (node (ref "Q4") (pin "4") (pinfunction "G_4") (pintype "input"))
    )
    (net (code "42") (name "Net-(L-GL2)") (class "Default")
      (node (ref "L") (pin "22") (pinfunction "GL2_22") (pintype "input"))
      (node (ref "Q3") (pin "4") (pinfunction "G_4") (pintype "input"))
    )
    (net (code "43") (name "Net-(L-VCP)") (class "Default")
      (node (ref "C48") (pin "2") (pinfunction "2_2") (pintype "input"))
      (node (ref "L") (pin "2") (pinfunction "VCP_2") (pintype "input"))
    )
    (net (code "44") (name "Net-(PRW-A)") (class "Default")
      (node (ref "PRW") (pin "2") (pinfunction "A_2") (pintype "input"))
      (node (ref "R43") (pin "1") (pinfunction "1_1") (pintype "input"))
    )
    (net (code "45") (name "Net-(Q5-G)") (class "Default")
      (node (ref "Q5") (pin "4") (pinfunction "G_4") (pintype "input"))
      (node (ref "R") (pin "24") (pinfunction "GH2_24") (pintype "input"))
    )
    (net (code "46") (name "Net-(Q6-G)") (class "Default")
      (node (ref "Q6") (pin "4") (pinfunction "G_4") (pintype "input"))
      (node (ref "R") (pin "17") (pinfunction "GH1_17") (pintype "input"))
    )
    (net (code "47") (name "Net-(Q7-G)") (class "Default")
      (node (ref "Q7") (pin "4") (pinfunction "G_4") (pintype "input"))
      (node (ref "R") (pin "22") (pinfunction "GL2_22") (pintype "input"))
    )
    (net (code "48") (name "Net-(Q8-G)") (class "Default")
      (node (ref "Q8") (pin "4") (pinfunction "G_4") (pintype "input"))
      (node (ref "R") (pin "19") (pinfunction "GL1_19") (pintype "input"))
    )
    (net (code "49") (name "Net-(R-AVDD)") (class "Default")
      (node (ref "C56") (pin "1") (pinfunction "1_1") (pintype "input"))
      (node (ref "R") (pin "12") (pinfunction "IDRIVE_12") (pintype "input"))
      (node (ref "R") (pin "6") (pinfunction "VREF_6") (pintype "input"))
      (node (ref "R") (pin "7") (pinfunction "AVDD_7") (pintype "input"))
    )
    (net (code "50") (name "Net-(R-CPH)") (class "Default")
      (node (ref "C53") (pin "1") (pinfunction "1_1") (pintype "input"))
      (node (ref "R") (pin "3") (pinfunction "CPH_3") (pintype "input"))
    )
    (net (code "51") (name "Net-(R-CPL)") (class "Default")
      (node (ref "C53") (pin "2") (pinfunction "2_2") (pintype "input"))
      (node (ref "R") (pin "4") (pinfunction "CPL_4") (pintype "input"))
    )
    (net (code "52") (name "Net-(R-DVDD)") (class "Default")
      (node (ref "C12") (pin "1") (pinfunction "1_1") (pintype "input"))
      (node (ref "R") (pin "8") (pinfunction "DVDD_8") (pintype "input"))
    )
    (net (code "53") (name "Net-(R-VCP)") (class "Default")
      (node (ref "C7") (pin "2") (pinfunction "2_2") (pintype "input"))
      (node (ref "R") (pin "2") (pinfunction "VCP_2") (pintype "input"))
    )
    (net (code "54") (name "VIN") (class "Default")
      (node (ref "C13") (pin "1") (pinfunction "1_1") (pintype "input"))
      (node (ref "CN2") (pin "2") (pinfunction "2_2") (pintype "unspecified"))
      (node (ref "D1") (pin "2") (pinfunction "A_2") (pintype "input"))
      (node (ref "D2") (pin "2") (pinfunction "A_2") (pintype "input"))
      (node (ref "D3") (pin "2") (pinfunction "A_2") (pintype "input"))
      (node (ref "Q1") (pin "5") (pinfunction "D_5") (pintype "input"))
      (node (ref "Q1") (pin "6") (pinfunction "D_6") (pintype "input"))
      (node (ref "Q1") (pin "7") (pinfunction "D_7") (pintype "input"))
      (node (ref "Q1") (pin "8") (pinfunction "D_8") (pintype "input"))
      (node (ref "Q1") (pin "9") (pinfunction "D_9") (pintype "input"))
      (node (ref "Q11") (pin "5") (pinfunction "D_5") (pintype "input"))
      (node (ref "Q11") (pin "6") (pinfunction "D_6") (pintype "input"))
      (node (ref "Q11") (pin "7") (pinfunction "D_7") (pintype "input"))
      (node (ref "Q11") (pin "8") (pinfunction "D_8") (pintype "input"))
      (node (ref "Q11") (pin "9") (pinfunction "D_9") (pintype "input"))
      (node (ref "Q2") (pin "5") (pinfunction "D_5") (pintype "input"))
      (node (ref "Q2") (pin "6") (pinfunction "D_6") (pintype "input"))
      (node (ref "Q2") (pin "7") (pinfunction "D_7") (pintype "input"))
      (node (ref "Q2") (pin "8") (pinfunction "D_8") (pintype "input"))
      (node (ref "Q2") (pin "9") (pinfunction "D_9") (pintype "input"))
      (node (ref "Q5") (pin "5") (pinfunction "D_5") (pintype "input"))
      (node (ref "Q5") (pin "6") (pinfunction "D_6") (pintype "input"))
      (node (ref "Q5") (pin "7") (pinfunction "D_7") (pintype "input"))
      (node (ref "Q5") (pin "8") (pinfunction "D_8") (pintype "input"))
      (node (ref "Q5") (pin "9") (pinfunction "D_9") (pintype "input"))
      (node (ref "Q6") (pin "5") (pinfunction "D_5") (pintype "input"))
      (node (ref "Q6") (pin "6") (pinfunction "D_6") (pintype "input"))
      (node (ref "Q6") (pin "7") (pinfunction "D_7") (pintype "input"))
      (node (ref "Q6") (pin "8") (pinfunction "D_8") (pintype "input"))
      (node (ref "Q6") (pin "9") (pinfunction "D_9") (pintype "input"))
      (node (ref "Q9") (pin "5") (pinfunction "D_5") (pintype "input"))
      (node (ref "Q9") (pin "6") (pinfunction "D_6") (pintype "input"))
      (node (ref "Q9") (pin "7") (pinfunction "D_7") (pintype "input"))
      (node (ref "Q9") (pin "8") (pinfunction "D_8") (pintype "input"))
      (node (ref "Q9") (pin "9") (pinfunction "D_9") (pintype "input"))
      (node (ref "R34") (pin "1") (pinfunction "1_1") (pintype "input"))
    )
    (net (code "55") (name "unconnected-(B-SNSOUT-Pad10)") (class "Default")
      (node (ref "B") (pin "10") (pinfunction "SNSOUT_10") (pintype "input+no_connect"))
    )
    (net (code "56") (name "unconnected-(B-SO-Pad11)") (class "Default")
      (node (ref "B") (pin "11") (pinfunction "SO_11") (pintype "input+no_connect"))
    )
    (net (code "57") (name "unconnected-(B-nFAULT-Pad9)") (class "Default")
      (node (ref "B") (pin "9") (pinfunction "nFAULT_9") (pintype "input+no_connect"))
    )
    (net (code "58") (name "unconnected-(CN2-Pad3)") (class "Default")
      (node (ref "CN2") (pin "3") (pinfunction "3_3") (pintype "unspecified"))
    )
    (net (code "59") (name "unconnected-(CN2-Pad4)") (class "Default")
      (node (ref "CN2") (pin "4") (pinfunction "4_4") (pintype "unspecified"))
    )
    (net (code "60") (name "unconnected-(CN3-Pad3)") (class "Default")
      (node (ref "CN3") (pin "3") (pinfunction "3_3") (pintype "unspecified"))
    )
    (net (code "61") (name "unconnected-(CN3-Pad4)") (class "Default")
      (node (ref "CN3") (pin "4") (pinfunction "4_4") (pintype "unspecified"))
    )
    (net (code "62") (name "unconnected-(CN4-Pad3)") (class "Default")
      (node (ref "CN4") (pin "3") (pinfunction "3_3") (pintype "unspecified"))
    )
    (net (code "63") (name "unconnected-(CN4-Pad4)") (class "Default")
      (node (ref "CN4") (pin "4") (pinfunction "4_4") (pintype "unspecified"))
    )
    (net (code "64") (name "unconnected-(CN5-Pad3)") (class "Default")
      (node (ref "CN5") (pin "3") (pinfunction "3_3") (pintype "unspecified"))
    )
    (net (code "65") (name "unconnected-(CN5-Pad4)") (class "Default")
      (node (ref "CN5") (pin "4") (pinfunction "4_4") (pintype "unspecified"))
    )
    (net (code "66") (name "unconnected-(L-SNSOUT-Pad10)") (class "Default")
      (node (ref "L") (pin "10") (pinfunction "SNSOUT_10") (pintype "input+no_connect"))
    )
    (net (code "67") (name "unconnected-(L-SO-Pad11)") (class "Default")
      (node (ref "L") (pin "11") (pinfunction "SO_11") (pintype "input+no_connect"))
    )
    (net (code "68") (name "unconnected-(L-nFAULT-Pad9)") (class "Default")
      (node (ref "L") (pin "9") (pinfunction "nFAULT_9") (pintype "input+no_connect"))
    )
    (net (code "69") (name "unconnected-(R-SNSOUT-Pad10)") (class "Default")
      (node (ref "R") (pin "10") (pinfunction "SNSOUT_10") (pintype "input+no_connect"))
    )
    (net (code "70") (name "unconnected-(R-SO-Pad11)") (class "Default")
      (node (ref "R") (pin "11") (pinfunction "SO_11") (pintype "input+no_connect"))
    )
    (net (code "71") (name "unconnected-(R-nFAULT-Pad9)") (class "Default")
      (node (ref "R") (pin "9") (pinfunction "nFAULT_9") (pintype "input+no_connect"))
    )
    (net (code "72") (name "unconnected-(U43-A6-Pad8)") (class "Default")
      (node (ref "U43") (pin "8") (pinfunction "A6_8") (pintype "unspecified+no_connect"))
    )
    (net (code "73") (name "unconnected-(U43-A7-Pad9)") (class "Default")
      (node (ref "U43") (pin "9") (pinfunction "A7_9") (pintype "unspecified+no_connect"))
    )
    (net (code "74") (name "unconnected-(U43-B6-Pad12)") (class "Default")
      (node (ref "U43") (pin "12") (pinfunction "B6_12") (pintype "unspecified+no_connect"))
    )
    (net (code "75") (name "unconnected-(U43-B7-Pad11)") (class "Default")
      (node (ref "U43") (pin "11") (pinfunction "B7_11") (pintype "unspecified+no_connect"))
    )
    (net (code "76") (name "unconnected-(U44-Pad3)") (class "Default")
      (node (ref "U44") (pin "3") (pinfunction "3_3") (pintype "unspecified+no_connect"))
    )
  )
)
